# 04_ANALOG_2.net
KiCad netlist of a schematic drawn in Altium Designer
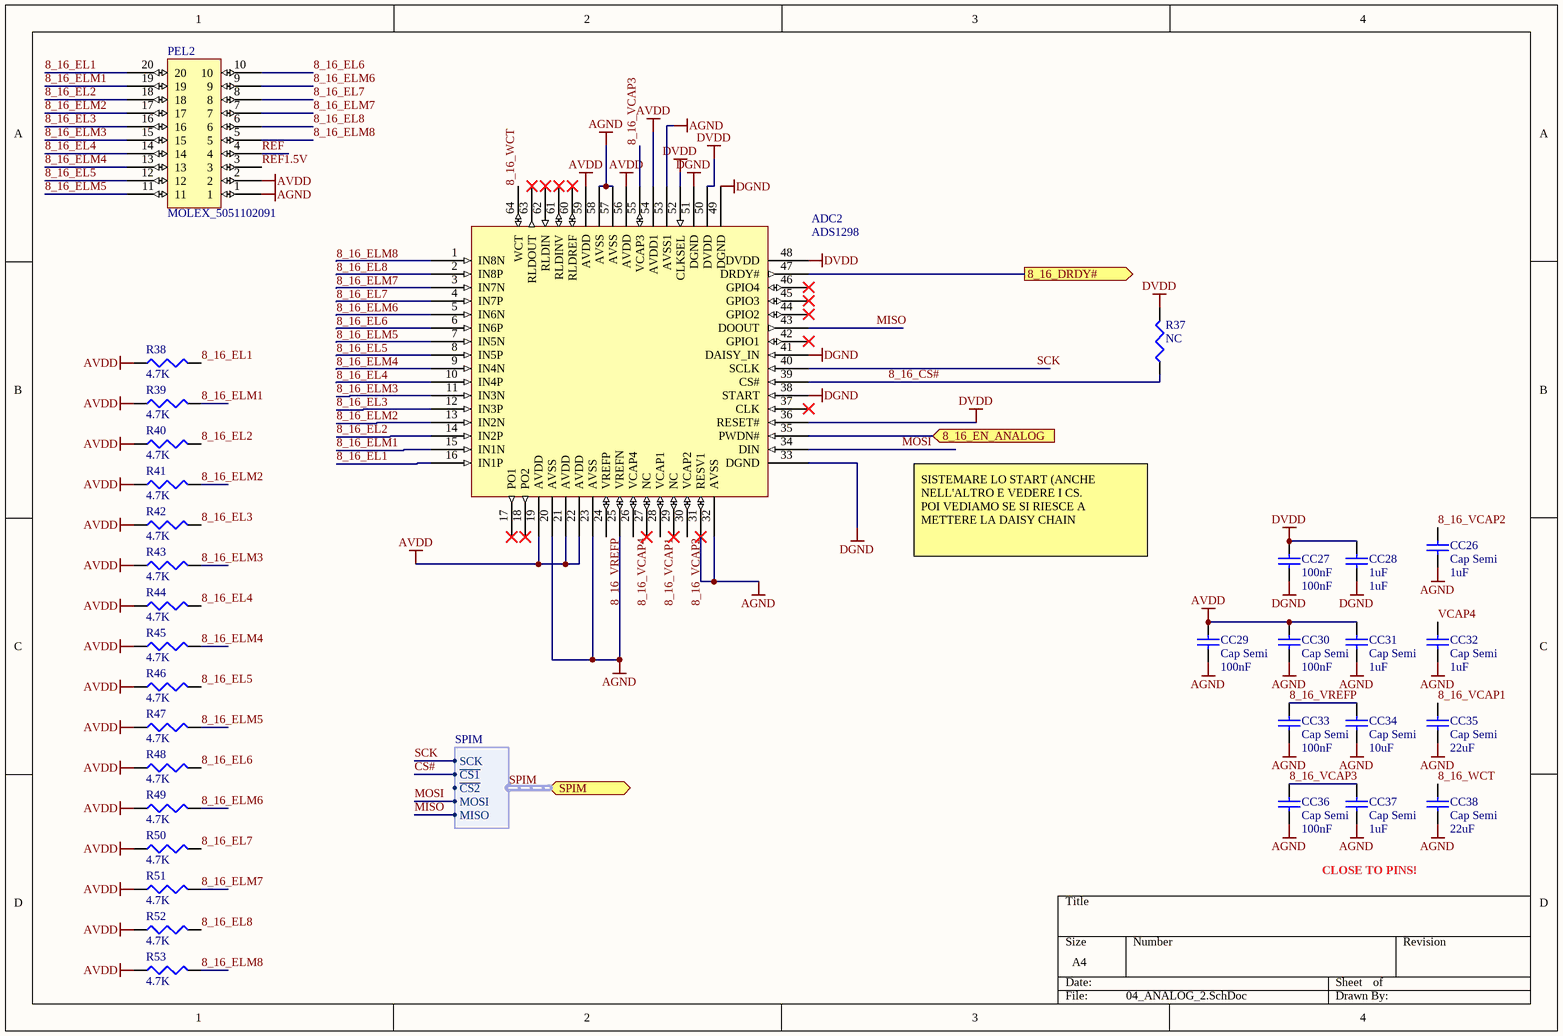
[diagram p0: 04_ANALOG_2.SchDoc]

(export (version "E")
  (design (tool "Eeschema 10.0.6"))
  (components
    (comp (ref "ADC2")
      (value "ADS1298")
      (footprint "Demo_Board_library_PCB:S-PQFP - G64 - ADS1298")
      (libsource (lib "Schlib1") (part "ADS1298"))
    )
    (comp (ref "CC26")
      (value "Cap Semi")
      (footprint "0402")
      (description "Capacitor (Semiconductor SIM Model)")
      (fields (field (name "ALTIUM_VALUE") "1uF") (field (name "PUBLISHER") "Altium Limited"))
      (libsource (lib "Miscellaneous Devices") (part "Cap Semi"))
    )
    (comp (ref "CC27")
      (value "100nF")
      (footprint "0402")
      (description "Capacitor (Semiconductor SIM Model)")
      (fields (field (name "ALTIUM_VALUE") "100nF") (field (name "PUBLISHER") "Altium Limited"))
      (libsource (lib "Miscellaneous Devices") (part "Cap Semi"))
    )
    (comp (ref "CC28")
      (value "1uF")
      (footprint "0402")
      (description "Capacitor (Semiconductor SIM Model)")
      (fields (field (name "ALTIUM_VALUE") "1uF") (field (name "PUBLISHER") "Altium Limited"))
      (libsource (lib "Miscellaneous Devices") (part "Cap Semi"))
    )
    (comp (ref "CC29")
      (value "Cap Semi")
      (footprint "0402")
      (description "Capacitor (Semiconductor SIM Model)")
      (fields (field (name "ALTIUM_VALUE") "100nF") (field (name "PUBLISHER") "Altium Limited"))
      (libsource (lib "Miscellaneous Devices") (part "Cap Semi"))
    )
    (comp (ref "CC30")
      (value "Cap Semi")
      (footprint "0402")
      (description "Capacitor (Semiconductor SIM Model)")
      (fields (field (name "ALTIUM_VALUE") "100nF") (field (name "PUBLISHER") "Altium Limited"))
      (libsource (lib "Miscellaneous Devices") (part "Cap Semi"))
    )
    (comp (ref "CC31")
      (value "Cap Semi")
      (footprint "0402")
      (description "Capacitor (Semiconductor SIM Model)")
      (fields (field (name "ALTIUM_VALUE") "1uF") (field (name "PUBLISHER") "Altium Limited"))
      (libsource (lib "Miscellaneous Devices") (part "Cap Semi"))
    )
    (comp (ref "CC32")
      (value "Cap Semi")
      (footprint "0402")
      (description "Capacitor (Semiconductor SIM Model)")
      (fields (field (name "ALTIUM_VALUE") "1uF") (field (name "PUBLISHER") "Altium Limited"))
      (libsource (lib "Miscellaneous Devices") (part "Cap Semi"))
    )
    (comp (ref "CC33")
      (value "Cap Semi")
      (footprint "0402")
      (description "Capacitor (Semiconductor SIM Model)")
      (fields (field (name "ALTIUM_VALUE") "100nF") (field (name "PUBLISHER") "Altium Limited"))
      (libsource (lib "Miscellaneous Devices") (part "Cap Semi"))
    )
    (comp (ref "CC34")
      (value "Cap Semi")
      (footprint "0402")
      (description "Capacitor (Semiconductor SIM Model)")
      (fields (field (name "ALTIUM_VALUE") "10uF") (field (name "PUBLISHER") "Altium Limited"))
      (libsource (lib "Miscellaneous Devices") (part "Cap Semi"))
    )
    (comp (ref "CC35")
      (value "Cap Semi")
      (footprint "J1-0603")
      (description "Capacitor (Semiconductor SIM Model)")
      (fields (field (name "ALTIUM_VALUE") "22uF") (field (name "PUBLISHER") "Altium Limited"))
      (libsource (lib "Miscellaneous Devices") (part "Cap Semi"))
    )
    (comp (ref "CC36")
      (value "Cap Semi")
      (footprint "0402")
      (description "Capacitor (Semiconductor SIM Model)")
      (fields (field (name "ALTIUM_VALUE") "100nF") (field (name "PUBLISHER") "Altium Limited"))
      (libsource (lib "Miscellaneous Devices") (part "Cap Semi"))
    )
    (comp (ref "CC37")
      (value "Cap Semi")
      (footprint "0402")
      (description "Capacitor (Semiconductor SIM Model)")
      (fields (field (name "ALTIUM_VALUE") "1uF") (field (name "PUBLISHER") "Altium Limited"))
      (libsource (lib "Miscellaneous Devices") (part "Cap Semi"))
    )
    (comp (ref "CC38")
      (value "Cap Semi")
      (footprint "1608[0603]")
      (description "Capacitor (Semiconductor SIM Model)")
      (fields (field (name "ALTIUM_VALUE") "22uF") (field (name "PUBLISHER") "Altium Limited"))
      (libsource (lib "Miscellaneous Devices") (part "Cap Semi"))
    )
    (comp (ref "PEL2")
      (value "MOLEX_5051102091")
      (footprint "MOLEX_5051102091")
      (libsource (lib "Schlib1") (part "MOLEX_5051102091"))
    )
    (comp (ref "R37")
      (value "NC")
      (footprint "0402")
      (description "Resistor")
      (fields (field (name "PUBLISHER") "Altium Limited"))
      (libsource (lib "Miscellaneous Devices") (part "Res3"))
    )
    (comp (ref "R38")
      (value "4.7K")
      (footprint "0402")
      (description "Resistor")
      (fields (field (name "PUBLISHER") "Altium Limited"))
      (libsource (lib "Miscellaneous Devices") (part "Res3"))
    )
    (comp (ref "R39")
      (value "4.7K")
      (footprint "0402")
      (description "Resistor")
      (fields (field (name "PUBLISHER") "Altium Limited"))
      (libsource (lib "Miscellaneous Devices") (part "Res3"))
    )
    (comp (ref "R40")
      (value "4.7K")
      (footprint "0402")
      (description "Resistor")
      (fields (field (name "PUBLISHER") "Altium Limited"))
      (libsource (lib "Miscellaneous Devices") (part "Res3"))
    )
    (comp (ref "R41")
      (value "4.7K")
      (footprint "0402")
      (description "Resistor")
      (fields (field (name "PUBLISHER") "Altium Limited"))
      (libsource (lib "Miscellaneous Devices") (part "Res3"))
    )
    (comp (ref "R42")
      (value "4.7K")
      (footprint "0402")
      (description "Resistor")
      (fields (field (name "PUBLISHER") "Altium Limited"))
      (libsource (lib "Miscellaneous Devices") (part "Res3"))
    )
    (comp (ref "R43")
      (value "4.7K")
      (footprint "0402")
      (description "Resistor")
      (fields (field (name "PUBLISHER") "Altium Limited"))
      (libsource (lib "Miscellaneous Devices") (part "Res3"))
    )
    (comp (ref "R44")
      (value "4.7K")
      (footprint "0402")
      (description "Resistor")
      (fields (field (name "PUBLISHER") "Altium Limited"))
      (libsource (lib "Miscellaneous Devices") (part "Res3"))
    )
    (comp (ref "R45")
      (value "4.7K")
      (footprint "0402")
      (description "Resistor")
      (fields (field (name "PUBLISHER") "Altium Limited"))
      (libsource (lib "Miscellaneous Devices") (part "Res3"))
    )
    (comp (ref "R46")
      (value "4.7K")
      (footprint "0402")
      (description "Resistor")
      (fields (field (name "PUBLISHER") "Altium Limited"))
      (libsource (lib "Miscellaneous Devices") (part "Res3"))
    )
    (comp (ref "R47")
      (value "4.7K")
      (footprint "0402")
      (description "Resistor")
      (fields (field (name "PUBLISHER") "Altium Limited"))
      (libsource (lib "Miscellaneous Devices") (part "Res3"))
    )
    (comp (ref "R48")
      (value "4.7K")
      (footprint "0402")
      (description "Resistor")
      (fields (field (name "PUBLISHER") "Altium Limited"))
      (libsource (lib "Miscellaneous Devices") (part "Res3"))
    )
    (comp (ref "R49")
      (value "4.7K")
      (footprint "0402")
      (description "Resistor")
      (fields (field (name "PUBLISHER") "Altium Limited"))
      (libsource (lib "Miscellaneous Devices") (part "Res3"))
    )
    (comp (ref "R50")
      (value "4.7K")
      (footprint "0402")
      (description "Resistor")
      (fields (field (name "PUBLISHER") "Altium Limited"))
      (libsource (lib "Miscellaneous Devices") (part "Res3"))
    )
    (comp (ref "R51")
      (value "4.7K")
      (footprint "0402")
      (description "Resistor")
      (fields (field (name "PUBLISHER") "Altium Limited"))
      (libsource (lib "Miscellaneous Devices") (part "Res3"))
    )
    (comp (ref "R52")
      (value "4.7K")
      (footprint "0402")
      (description "Resistor")
      (fields (field (name "PUBLISHER") "Altium Limited"))
      (libsource (lib "Miscellaneous Devices") (part "Res3"))
    )
    (comp (ref "R53")
      (value "4.7K")
      (footprint "0402")
      (description "Resistor")
      (fields (field (name "PUBLISHER") "Altium Limited"))
      (libsource (lib "Miscellaneous Devices") (part "Res3"))
    )
  )
  (nets
    (net (code "2") (name "/8_16_CS#") (class "Default")
      (node (ref "ADC2") (pin "39") (pinfunction "CS#_39") (pintype "input"))
      (node (ref "R37") (pin "1") (pinfunction "1_1") (pintype "passive"))
    )
    (net (code "3") (name "/8_16_DRDY#") (class "Default")
      (node (ref "ADC2") (pin "47") (pinfunction "DRDY#_47") (pintype "output"))
    )
    (net (code "4") (name "/8_16_EL1") (class "Default")
      (node (ref "ADC2") (pin "16") (pinfunction "IN1P_16") (pintype "input"))
      (node (ref "PEL2") (pin "20") (pinfunction "20_20") (pintype "bidirectional"))
      (node (ref "R38") (pin "2") (pinfunction "2_2") (pintype "passive"))
    )
    (net (code "5") (name "/8_16_EL2") (class "Default")
      (node (ref "ADC2") (pin "14") (pinfunction "IN2P_14") (pintype "input"))
      (node (ref "PEL2") (pin "18") (pinfunction "18_18") (pintype "bidirectional"))
      (node (ref "R40") (pin "2") (pinfunction "2_2") (pintype "passive"))
    )
    (net (code "6") (name "/8_16_EL3") (class "Default")
      (node (ref "ADC2") (pin "12") (pinfunction "IN3P_12") (pintype "input"))
      (node (ref "PEL2") (pin "16") (pinfunction "16_16") (pintype "bidirectional"))
      (node (ref "R42") (pin "2") (pinfunction "2_2") (pintype "passive"))
    )
    (net (code "7") (name "/8_16_EL4") (class "Default")
      (node (ref "ADC2") (pin "10") (pinfunction "IN4P_10") (pintype "input"))
      (node (ref "PEL2") (pin "14") (pinfunction "14_14") (pintype "bidirectional"))
      (node (ref "R44") (pin "2") (pinfunction "2_2") (pintype "passive"))
    )
    (net (code "8") (name "/8_16_EL5") (class "Default")
      (node (ref "ADC2") (pin "8") (pinfunction "IN5P_8") (pintype "input"))
      (node (ref "PEL2") (pin "12") (pinfunction "12_12") (pintype "bidirectional"))
      (node (ref "R46") (pin "2") (pinfunction "2_2") (pintype "passive"))
    )
    (net (code "9") (name "/8_16_EL6") (class "Default")
      (node (ref "ADC2") (pin "6") (pinfunction "IN6P_6") (pintype "input"))
      (node (ref "PEL2") (pin "10") (pinfunction "10_10") (pintype "bidirectional"))
      (node (ref "R48") (pin "2") (pinfunction "2_2") (pintype "passive"))
    )
    (net (code "10") (name "/8_16_EL7") (class "Default")
      (node (ref "ADC2") (pin "4") (pinfunction "IN7P_4") (pintype "input"))
      (node (ref "PEL2") (pin "8") (pinfunction "8_8") (pintype "bidirectional"))
      (node (ref "R50") (pin "2") (pinfunction "2_2") (pintype "passive"))
    )
    (net (code "11") (name "/8_16_EL8") (class "Default")
      (node (ref "ADC2") (pin "2") (pinfunction "IN8P_2") (pintype "input"))
      (node (ref "PEL2") (pin "6") (pinfunction "6_6") (pintype "bidirectional"))
      (node (ref "R52") (pin "2") (pinfunction "2_2") (pintype "passive"))
    )
    (net (code "12") (name "/8_16_ELM1") (class "Default")
      (node (ref "ADC2") (pin "15") (pinfunction "IN1N_15") (pintype "input"))
      (node (ref "PEL2") (pin "19") (pinfunction "19_19") (pintype "bidirectional"))
      (node (ref "R39") (pin "2") (pinfunction "2_2") (pintype "passive"))
    )
    (net (code "13") (name "/8_16_ELM2") (class "Default")
      (node (ref "ADC2") (pin "13") (pinfunction "IN2N_13") (pintype "input"))
      (node (ref "PEL2") (pin "17") (pinfunction "17_17") (pintype "bidirectional"))
      (node (ref "R41") (pin "2") (pinfunction "2_2") (pintype "passive"))
    )
    (net (code "14") (name "/8_16_ELM3") (class "Default")
      (node (ref "ADC2") (pin "11") (pinfunction "IN3N_11") (pintype "input"))
      (node (ref "PEL2") (pin "15") (pinfunction "15_15") (pintype "bidirectional"))
      (node (ref "R43") (pin "2") (pinfunction "2_2") (pintype "passive"))
    )
    (net (code "15") (name "/8_16_ELM4") (class "Default")
      (node (ref "ADC2") (pin "9") (pinfunction "IN4N_9") (pintype "input"))
      (node (ref "PEL2") (pin "13") (pinfunction "13_13") (pintype "bidirectional"))
      (node (ref "R45") (pin "2") (pinfunction "2_2") (pintype "passive"))
    )
    (net (code "16") (name "/8_16_ELM5") (class "Default")
      (node (ref "ADC2") (pin "7") (pinfunction "IN5N_7") (pintype "input"))
      (node (ref "PEL2") (pin "11") (pinfunction "11_11") (pintype "bidirectional"))
      (node (ref "R47") (pin "2") (pinfunction "2_2") (pintype "passive"))
    )
    (net (code "17") (name "/8_16_ELM6") (class "Default")
      (node (ref "ADC2") (pin "5") (pinfunction "IN6N_5") (pintype "input"))
      (node (ref "PEL2") (pin "9") (pinfunction "9_9") (pintype "bidirectional"))
      (node (ref "R49") (pin "2") (pinfunction "2_2") (pintype "passive"))
    )
    (net (code "18") (name "/8_16_ELM7") (class "Default")
      (node (ref "ADC2") (pin "3") (pinfunction "IN7N_3") (pintype "input"))
      (node (ref "PEL2") (pin "7") (pinfunction "7_7") (pintype "bidirectional"))
      (node (ref "R51") (pin "2") (pinfunction "2_2") (pintype "passive"))
    )
    (net (code "19") (name "/8_16_ELM8") (class "Default")
      (node (ref "ADC2") (pin "1") (pinfunction "IN8N_1") (pintype "input"))
      (node (ref "PEL2") (pin "5") (pinfunction "5_5") (pintype "bidirectional"))
      (node (ref "R53") (pin "2") (pinfunction "2_2") (pintype "passive"))
    )
    (net (code "20") (name "/8_16_EN_ANALOG") (class "Default")
      (node (ref "ADC2") (pin "35") (pinfunction "PWDN#_35") (pintype "input"))
    )
    (net (code "21") (name "/8_16_VCAP1") (class "Default")
      (node (ref "ADC2") (pin "28") (pinfunction "VCAP1_28") (pintype "bidirectional"))
      (node (ref "CC35") (pin "2") (pinfunction "2_2") (pintype "passive"))
    )
    (net (code "22") (name "/8_16_VCAP2") (class "Default")
      (node (ref "ADC2") (pin "30") (pinfunction "VCAP2_30") (pintype "bidirectional"))
      (node (ref "CC26") (pin "2") (pinfunction "2_2") (pintype "passive"))
    )
    (net (code "23") (name "/8_16_VCAP3") (class "Default")
      (node (ref "ADC2") (pin "55") (pinfunction "VCAP3_55") (pintype "bidirectional"))
      (node (ref "CC36") (pin "2") (pinfunction "2_2") (pintype "passive"))
      (node (ref "CC37") (pin "2") (pinfunction "2_2") (pintype "passive"))
    )
    (net (code "24") (name "/8_16_VCAP4") (class "Default")
      (node (ref "ADC2") (pin "26") (pinfunction "VCAP4_26") (pintype "bidirectional"))
    )
    (net (code "25") (name "/8_16_VREFP") (class "Default")
      (node (ref "ADC2") (pin "24") (pinfunction "VREFP_24") (pintype "bidirectional"))
      (node (ref "CC33") (pin "2") (pinfunction "2_2") (pintype "passive"))
      (node (ref "CC34") (pin "2") (pinfunction "2_2") (pintype "passive"))
    )
    (net (code "26") (name "/8_16_WCT") (class "Default")
      (node (ref "ADC2") (pin "64") (pinfunction "WCT_64") (pintype "bidirectional"))
      (node (ref "CC38") (pin "2") (pinfunction "2_2") (pintype "passive"))
    )
    (net (code "28") (name "/MISO") (class "Default")
      (node (ref "ADC2") (pin "43") (pinfunction "DOOUT_43") (pintype "output"))
    )
    (net (code "29") (name "/MOSI") (class "Default")
      (node (ref "ADC2") (pin "34") (pinfunction "DIN_34") (pintype "input"))
    )
    (net (code "30") (name "/REF") (class "Default")
      (node (ref "PEL2") (pin "4") (pinfunction "4_4") (pintype "bidirectional"))
    )
    (net (code "31") (name "/REF1.5V") (class "Default")
      (node (ref "PEL2") (pin "3") (pinfunction "3_3") (pintype "bidirectional"))
    )
    (net (code "32") (name "/SCK") (class "Default")
      (node (ref "ADC2") (pin "40") (pinfunction "SCLK_40") (pintype "input"))
    )
    (net (code "34") (name "/VCAP4") (class "Default")
      (node (ref "CC32") (pin "2") (pinfunction "2_2") (pintype "passive"))
    )
    (net (code "35") (name "AGND") (class "Default")
      (node (ref "ADC2") (pin "20") (pinfunction "AVSS_20") (pintype "power_in"))
      (node (ref "ADC2") (pin "23") (pinfunction "AVSS_23") (pintype "power_in"))
      (node (ref "ADC2") (pin "25") (pinfunction "VREFN_25") (pintype "bidirectional"))
      (node (ref "ADC2") (pin "31") (pinfunction "RESV1_31") (pintype "bidirectional"))
      (node (ref "ADC2") (pin "32") (pinfunction "AVSS_32") (pintype "power_in"))
      (node (ref "ADC2") (pin "53") (pinfunction "AVSS1_53") (pintype "power_in"))
      (node (ref "ADC2") (pin "57") (pinfunction "AVSS_57") (pintype "power_in"))
      (node (ref "ADC2") (pin "58") (pinfunction "AVSS_58") (pintype "power_in"))
      (node (ref "CC26") (pin "1") (pinfunction "1_1") (pintype "passive"))
      (node (ref "CC29") (pin "1") (pinfunction "1_1") (pintype "passive"))
      (node (ref "CC30") (pin "1") (pinfunction "1_1") (pintype "passive"))
      (node (ref "CC31") (pin "1") (pinfunction "1_1") (pintype "passive"))
      (node (ref "CC32") (pin "1") (pinfunction "1_1") (pintype "passive"))
      (node (ref "CC33") (pin "1") (pinfunction "1_1") (pintype "passive"))
      (node (ref "CC34") (pin "1") (pinfunction "1_1") (pintype "passive"))
      (node (ref "CC35") (pin "1") (pinfunction "1_1") (pintype "passive"))
      (node (ref "CC36") (pin "1") (pinfunction "1_1") (pintype "passive"))
      (node (ref "CC37") (pin "1") (pinfunction "1_1") (pintype "passive"))
      (node (ref "CC38") (pin "1") (pinfunction "1_1") (pintype "passive"))
      (node (ref "PEL2") (pin "1") (pinfunction "1_1") (pintype "bidirectional"))
    )
    (net (code "36") (name "AVDD") (class "Default")
      (node (ref "ADC2") (pin "19") (pinfunction "AVDD_19") (pintype "power_in"))
      (node (ref "ADC2") (pin "21") (pinfunction "AVDD_21") (pintype "power_in"))
      (node (ref "ADC2") (pin "22") (pinfunction "AVDD_22") (pintype "power_in"))
      (node (ref "ADC2") (pin "54") (pinfunction "AVDD1_54") (pintype "power_in"))
      (node (ref "ADC2") (pin "56") (pinfunction "AVDD_56") (pintype "power_in"))
      (node (ref "ADC2") (pin "59") (pinfunction "AVDD_59") (pintype "power_in"))
      (node (ref "CC29") (pin "2") (pinfunction "2_2") (pintype "passive"))
      (node (ref "CC30") (pin "2") (pinfunction "2_2") (pintype "passive"))
      (node (ref "CC31") (pin "2") (pinfunction "2_2") (pintype "passive"))
      (node (ref "PEL2") (pin "2") (pinfunction "2_2") (pintype "bidirectional"))
      (node (ref "R38") (pin "1") (pinfunction "1_1") (pintype "passive"))
      (node (ref "R39") (pin "1") (pinfunction "1_1") (pintype "passive"))
      (node (ref "R40") (pin "1") (pinfunction "1_1") (pintype "passive"))
      (node (ref "R41") (pin "1") (pinfunction "1_1") (pintype "passive"))
      (node (ref "R42") (pin "1") (pinfunction "1_1") (pintype "passive"))
      (node (ref "R43") (pin "1") (pinfunction "1_1") (pintype "passive"))
      (node (ref "R44") (pin "1") (pinfunction "1_1") (pintype "passive"))
      (node (ref "R45") (pin "1") (pinfunction "1_1") (pintype "passive"))
      (node (ref "R46") (pin "1") (pinfunction "1_1") (pintype "passive"))
      (node (ref "R47") (pin "1") (pinfunction "1_1") (pintype "passive"))
      (node (ref "R48") (pin "1") (pinfunction "1_1") (pintype "passive"))
      (node (ref "R49") (pin "1") (pinfunction "1_1") (pintype "passive"))
      (node (ref "R50") (pin "1") (pinfunction "1_1") (pintype "passive"))
      (node (ref "R51") (pin "1") (pinfunction "1_1") (pintype "passive"))
      (node (ref "R52") (pin "1") (pinfunction "1_1") (pintype "passive"))
      (node (ref "R53") (pin "1") (pinfunction "1_1") (pintype "passive"))
    )
    (net (code "37") (name "DGND") (class "Default")
      (node (ref "ADC2") (pin "33") (pinfunction "DGND_33") (pintype "power_in"))
      (node (ref "ADC2") (pin "38") (pinfunction "START_38") (pintype "input"))
      (node (ref "ADC2") (pin "41") (pinfunction "DAISY_IN_41") (pintype "input"))
      (node (ref "ADC2") (pin "49") (pinfunction "DGND_49") (pintype "power_in"))
      (node (ref "ADC2") (pin "51") (pinfunction "DGND_51") (pintype "power_in"))
      (node (ref "CC27") (pin "1") (pinfunction "1_1") (pintype "passive"))
      (node (ref "CC28") (pin "1") (pinfunction "1_1") (pintype "passive"))
    )
    (net (code "38") (name "DVDD") (class "Default")
      (node (ref "ADC2") (pin "36") (pinfunction "RESET#_36") (pintype "input"))
      (node (ref "ADC2") (pin "48") (pinfunction "DVDD_48") (pintype "power_in"))
      (node (ref "ADC2") (pin "50") (pinfunction "DVDD_50") (pintype "power_in"))
      (node (ref "ADC2") (pin "52") (pinfunction "CLKSEL_52") (pintype "input"))
      (node (ref "CC27") (pin "2") (pinfunction "2_2") (pintype "passive"))
      (node (ref "CC28") (pin "2") (pinfunction "2_2") (pintype "passive"))
      (node (ref "R37") (pin "2") (pinfunction "2_2") (pintype "passive"))
    )
    (net (code "39") (name "unconnected-(ADC2-CLK-Pad37)") (class "Default")
      (node (ref "ADC2") (pin "37") (pinfunction "CLK_37") (pintype "input+no_connect"))
    )
    (net (code "40") (name "unconnected-(ADC2-GPIO1-Pad42)") (class "Default")
      (node (ref "ADC2") (pin "42") (pinfunction "GPIO1_42") (pintype "bidirectional+no_connect"))
    )
    (net (code "41") (name "unconnected-(ADC2-GPIO2-Pad44)") (class "Default")
      (node (ref "ADC2") (pin "44") (pinfunction "GPIO2_44") (pintype "bidirectional+no_connect"))
    )
    (net (code "42") (name "unconnected-(ADC2-GPIO3-Pad45)") (class "Default")
      (node (ref "ADC2") (pin "45") (pinfunction "GPIO3_45") (pintype "bidirectional+no_connect"))
    )
    (net (code "43") (name "unconnected-(ADC2-GPIO4-Pad46)") (class "Default")
      (node (ref "ADC2") (pin "46") (pinfunction "GPIO4_46") (pintype "bidirectional+no_connect"))
    )
    (net (code "44") (name "unconnected-(ADC2-NC-Pad27)") (class "Default")
      (node (ref "ADC2") (pin "27") (pinfunction "NC_27") (pintype "bidirectional+no_connect"))
    )
    (net (code "45") (name "unconnected-(ADC2-NC-Pad29)") (class "Default")
      (node (ref "ADC2") (pin "29") (pinfunction "NC_29") (pintype "bidirectional+no_connect"))
    )
    (net (code "46") (name "unconnected-(ADC2-PO1-Pad17)") (class "Default")
      (node (ref "ADC2") (pin "17") (pinfunction "PO1_17") (pintype "output+no_connect"))
    )
    (net (code "47") (name "unconnected-(ADC2-PO2-Pad18)") (class "Default")
      (node (ref "ADC2") (pin "18") (pinfunction "PO2_18") (pintype "output+no_connect"))
    )
    (net (code "48") (name "unconnected-(ADC2-RLDIN-Pad62)") (class "Default")
      (node (ref "ADC2") (pin "62") (pinfunction "RLDIN_62") (pintype "input+no_connect"))
    )
    (net (code "49") (name "unconnected-(ADC2-RLDINV-Pad61)") (class "Default")
      (node (ref "ADC2") (pin "61") (pinfunction "RLDINV_61") (pintype "bidirectional+no_connect"))
    )
    (net (code "50") (name "unconnected-(ADC2-RLDOUT-Pad63)") (class "Default")
      (node (ref "ADC2") (pin "63") (pinfunction "RLDOUT_63") (pintype "output+no_connect"))
    )
    (net (code "51") (name "unconnected-(ADC2-RLDREF-Pad60)") (class "Default")
      (node (ref "ADC2") (pin "60") (pinfunction "RLDREF_60") (pintype "bidirectional+no_connect"))
    )
  )
)
